# p2-101.net
KiCad netlist of a schematic drawn in EAGLE
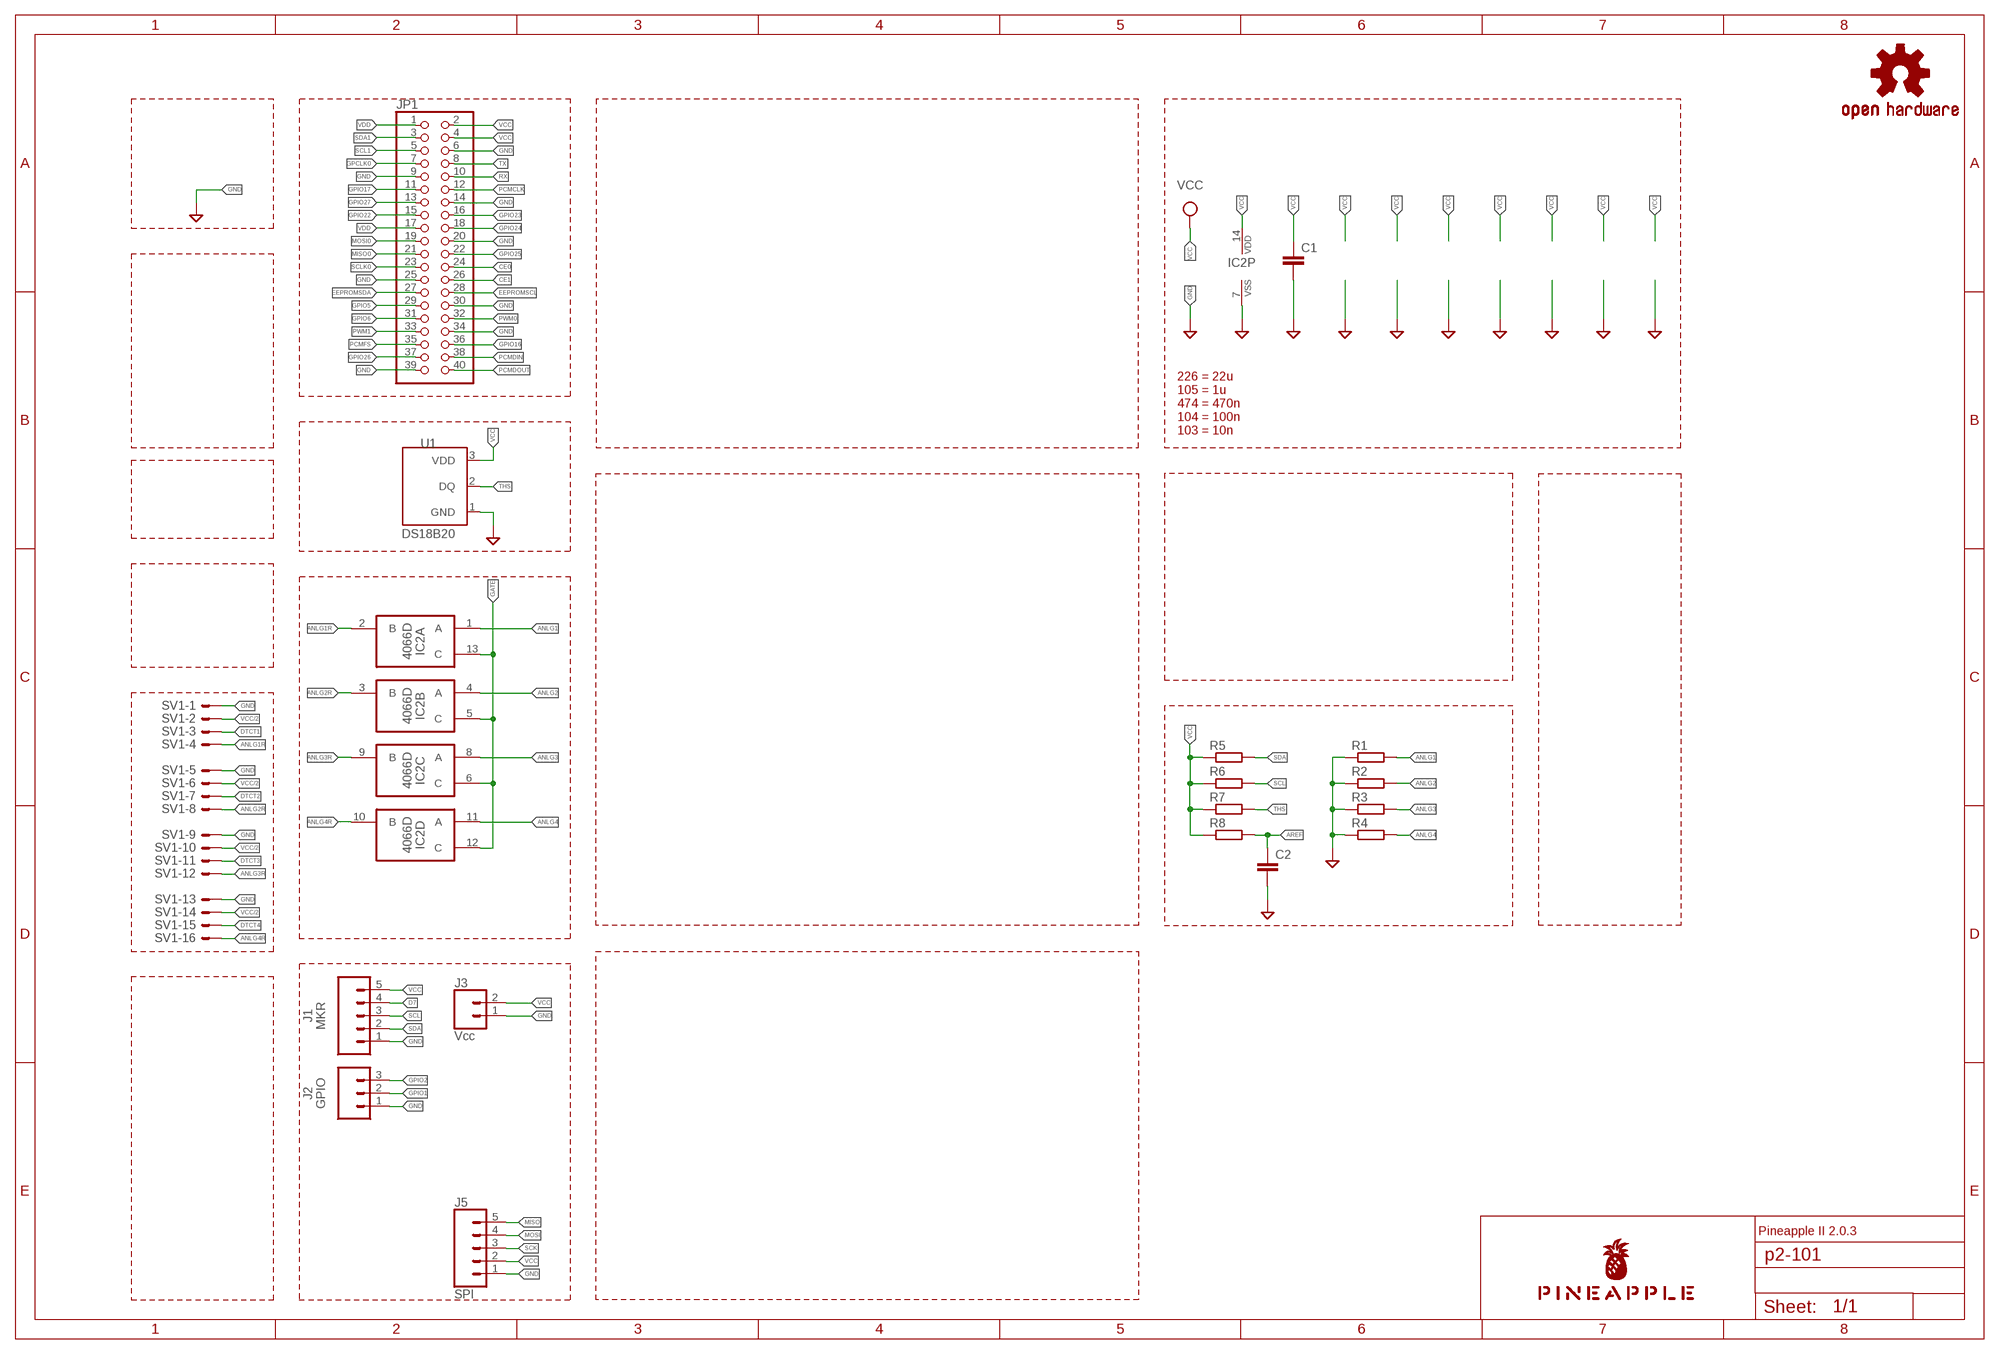
[diagram p0: schematic, sheet 1]

(export (version "E")
  (design (tool "Eeschema 10.0.6"))
  (components
    (comp (ref "C1")
      (value "C-EUC2012")
      (footprint "eagle-import:C2012")
      (libsource (lib "eagle-import") (part "C-EUC2012"))
    )
    (comp (ref "C2")
      (value "C-EUC2012")
      (footprint "eagle-import:C2012")
      (libsource (lib "eagle-import") (part "C-EUC2012"))
    )
    (comp (ref "IC2")
      (value "4066D")
      (footprint "eagle-import:SO14")
      (libsource (lib "eagle-import") (part "4066D"))
    )
    (comp (ref "J1")
      (value "MKR")
      (footprint "eagle-import:JST-5-PTH")
      (libsource (lib "eagle-import") (part "CONN_05JST"))
    )
    (comp (ref "J2")
      (value "GPIO")
      (footprint "eagle-import:JST-3-PTH")
      (libsource (lib "eagle-import") (part "CONN_03JST-PTH"))
    )
    (comp (ref "J3")
      (value "Vcc")
      (footprint "eagle-import:JST-2-PTH")
      (libsource (lib "eagle-import") (part "CONN_02JST-PTH-2"))
    )
    (comp (ref "J5")
      (value "SPI")
      (footprint "eagle-import:JST-5-PTH-VERT")
      (libsource (lib "eagle-import") (part "CONN_05JST-VERT"))
    )
    (comp (ref "JP1")
      (value "PINHD-2X20")
      (footprint "eagle-import:2X20")
      (libsource (lib "eagle-import") (part "PINHD-2X20"))
    )
    (comp (ref "LOGO1")
      (value "OSHW-LOGOS-COPPER")
      (footprint "eagle-import:OSHW-LOGO-S_COPPER")
      (libsource (lib "eagle-import") (part "OSHW-LOGOS-COPPER"))
    )
    (comp (ref "R1")
      (value "R-EU_M2012")
      (footprint "eagle-import:M2012")
      (libsource (lib "eagle-import") (part "R-EU_M2012"))
    )
    (comp (ref "R2")
      (value "R-EU_M2012")
      (footprint "eagle-import:M2012")
      (libsource (lib "eagle-import") (part "R-EU_M2012"))
    )
    (comp (ref "R3")
      (value "R-EU_M2012")
      (footprint "eagle-import:M2012")
      (libsource (lib "eagle-import") (part "R-EU_M2012"))
    )
    (comp (ref "R4")
      (value "R-EU_M2012")
      (footprint "eagle-import:M2012")
      (libsource (lib "eagle-import") (part "R-EU_M2012"))
    )
    (comp (ref "R5")
      (value "R-EU_M2012")
      (footprint "eagle-import:M2012")
      (libsource (lib "eagle-import") (part "R-EU_M2012"))
    )
    (comp (ref "R6")
      (value "R-EU_M2012")
      (footprint "eagle-import:M2012")
      (libsource (lib "eagle-import") (part "R-EU_M2012"))
    )
    (comp (ref "R7")
      (value "R-EU_M2012")
      (footprint "eagle-import:M2012")
      (libsource (lib "eagle-import") (part "R-EU_M2012"))
    )
    (comp (ref "R8")
      (value "R-EU_M2012")
      (footprint "eagle-import:M2012")
      (libsource (lib "eagle-import") (part "R-EU_M2012"))
    )
    (comp (ref "SV1")
      (value "ML16LE")
      (footprint "eagle-import:ML16L")
      (libsource (lib "eagle-import") (part "ML16LE"))
    )
    (comp (ref "U$1")
      (value "PINEAPPLE450_SILK")
      (footprint "eagle-import:PINEAPPLE450_SILK")
      (libsource (lib "eagle-import") (part "PINEAPPLE450_SILK"))
    )
    (comp (ref "U1")
      (value "DS18B20")
      (footprint "eagle-import:TO-92-AMMO")
      (libsource (lib "eagle-import") (part "DS18B20"))
    )
  )
  (nets
    (net (code "1") (name "ANLG1") (class "Default")
      (node (ref "IC2") (pin "1") (pinfunction "A_1") (pintype "tri_state"))
      (node (ref "R1") (pin "2") (pinfunction "2_2") (pintype "passive"))
    )
    (net (code "2") (name "ANLG1R") (class "Default")
      (node (ref "IC2") (pin "2") (pinfunction "B_2") (pintype "tri_state"))
      (node (ref "SV1") (pin "4") (pinfunction "S_4") (pintype "passive"))
    )
    (net (code "3") (name "ANLG2") (class "Default")
      (node (ref "IC2") (pin "4") (pinfunction "A_4") (pintype "tri_state"))
      (node (ref "R2") (pin "2") (pinfunction "2_2") (pintype "passive"))
    )
    (net (code "4") (name "ANLG2R") (class "Default")
      (node (ref "IC2") (pin "3") (pinfunction "B_3") (pintype "tri_state"))
      (node (ref "SV1") (pin "8") (pinfunction "S_8") (pintype "passive"))
    )
    (net (code "5") (name "ANLG3") (class "Default")
      (node (ref "IC2") (pin "8") (pinfunction "A_8") (pintype "tri_state"))
      (node (ref "R3") (pin "2") (pinfunction "2_2") (pintype "passive"))
    )
    (net (code "6") (name "ANLG3R") (class "Default")
      (node (ref "IC2") (pin "9") (pinfunction "B_9") (pintype "tri_state"))
      (node (ref "SV1") (pin "12") (pinfunction "S_12") (pintype "passive"))
    )
    (net (code "7") (name "ANLG4") (class "Default")
      (node (ref "IC2") (pin "11") (pinfunction "A_11") (pintype "tri_state"))
      (node (ref "R4") (pin "2") (pinfunction "2_2") (pintype "passive"))
    )
    (net (code "8") (name "ANLG4R") (class "Default")
      (node (ref "IC2") (pin "10") (pinfunction "B_10") (pintype "tri_state"))
      (node (ref "SV1") (pin "16") (pinfunction "S_16") (pintype "passive"))
    )
    (net (code "9") (name "AREF") (class "Default")
      (node (ref "C2") (pin "1") (pinfunction "1_1") (pintype "passive"))
      (node (ref "R8") (pin "2") (pinfunction "2_2") (pintype "passive"))
    )
    (net (code "10") (name "CE0") (class "Default")
      (node (ref "JP1") (pin "24") (pinfunction "24_24") (pintype "passive"))
    )
    (net (code "11") (name "CE1") (class "Default")
      (node (ref "JP1") (pin "26") (pinfunction "26_26") (pintype "passive"))
    )
    (net (code "12") (name "D7") (class "Default")
      (node (ref "J1") (pin "4") (pinfunction "4_4") (pintype "passive"))
    )
    (net (code "13") (name "DTCT1") (class "Default")
      (node (ref "SV1") (pin "3") (pinfunction "S_3") (pintype "passive"))
    )
    (net (code "14") (name "DTCT2") (class "Default")
      (node (ref "SV1") (pin "7") (pinfunction "S_7") (pintype "passive"))
    )
    (net (code "15") (name "DTCT3") (class "Default")
      (node (ref "SV1") (pin "11") (pinfunction "S_11") (pintype "passive"))
    )
    (net (code "16") (name "DTCT4") (class "Default")
      (node (ref "SV1") (pin "15") (pinfunction "S_15") (pintype "passive"))
    )
    (net (code "17") (name "EEPROMSCL") (class "Default")
      (node (ref "JP1") (pin "28") (pinfunction "28_28") (pintype "passive"))
    )
    (net (code "18") (name "EEPROMSDA") (class "Default")
      (node (ref "JP1") (pin "27") (pinfunction "27_27") (pintype "passive"))
    )
    (net (code "19") (name "GATE") (class "Default")
      (node (ref "IC2") (pin "12") (pinfunction "C_12") (pintype "input"))
      (node (ref "IC2") (pin "13") (pinfunction "C_13") (pintype "input"))
      (node (ref "IC2") (pin "5") (pinfunction "C_5") (pintype "input"))
      (node (ref "IC2") (pin "6") (pinfunction "C_6") (pintype "input"))
    )
    (net (code "20") (name "GND") (class "Default")
      (node (ref "C1") (pin "2") (pinfunction "2_2") (pintype "passive"))
      (node (ref "C2") (pin "2") (pinfunction "2_2") (pintype "passive"))
      (node (ref "IC2") (pin "7") (pinfunction "VSS_7") (pintype "power_in"))
      (node (ref "J1") (pin "1") (pinfunction "1_1") (pintype "passive"))
      (node (ref "J2") (pin "1") (pinfunction "1_1") (pintype "passive"))
      (node (ref "J3") (pin "1") (pinfunction "1_1") (pintype "passive"))
      (node (ref "J5") (pin "1") (pinfunction "1_1") (pintype "passive"))
      (node (ref "JP1") (pin "14") (pinfunction "14_14") (pintype "passive"))
      (node (ref "JP1") (pin "20") (pinfunction "20_20") (pintype "passive"))
      (node (ref "JP1") (pin "25") (pinfunction "25_25") (pintype "passive"))
      (node (ref "JP1") (pin "30") (pinfunction "30_30") (pintype "passive"))
      (node (ref "JP1") (pin "34") (pinfunction "34_34") (pintype "passive"))
      (node (ref "JP1") (pin "39") (pinfunction "39_39") (pintype "passive"))
      (node (ref "JP1") (pin "6") (pinfunction "6_6") (pintype "passive"))
      (node (ref "JP1") (pin "9") (pinfunction "9_9") (pintype "passive"))
      (node (ref "R1") (pin "1") (pinfunction "1_1") (pintype "passive"))
      (node (ref "R2") (pin "1") (pinfunction "1_1") (pintype "passive"))
      (node (ref "R3") (pin "1") (pinfunction "1_1") (pintype "passive"))
      (node (ref "R4") (pin "1") (pinfunction "1_1") (pintype "passive"))
      (node (ref "SV1") (pin "1") (pinfunction "S_1") (pintype "passive"))
      (node (ref "SV1") (pin "13") (pinfunction "S_13") (pintype "passive"))
      (node (ref "SV1") (pin "5") (pinfunction "S_5") (pintype "passive"))
      (node (ref "SV1") (pin "9") (pinfunction "S_9") (pintype "passive"))
      (node (ref "U1") (pin "1") (pinfunction "GND_1") (pintype "power_in"))
    )
    (net (code "21") (name "GPCLK0") (class "Default")
      (node (ref "JP1") (pin "7") (pinfunction "7_7") (pintype "passive"))
    )
    (net (code "22") (name "GPIO1") (class "Default")
      (node (ref "J2") (pin "2") (pinfunction "2_2") (pintype "passive"))
    )
    (net (code "23") (name "GPIO2") (class "Default")
      (node (ref "J2") (pin "3") (pinfunction "3_3") (pintype "passive"))
    )
    (net (code "24") (name "GPIO5") (class "Default")
      (node (ref "JP1") (pin "29") (pinfunction "29_29") (pintype "passive"))
    )
    (net (code "25") (name "GPIO6") (class "Default")
      (node (ref "JP1") (pin "31") (pinfunction "31_31") (pintype "passive"))
    )
    (net (code "26") (name "GPIO16") (class "Default")
      (node (ref "JP1") (pin "36") (pinfunction "36_36") (pintype "passive"))
    )
    (net (code "27") (name "GPIO17") (class "Default")
      (node (ref "JP1") (pin "11") (pinfunction "11_11") (pintype "passive"))
    )
    (net (code "28") (name "GPIO22") (class "Default")
      (node (ref "JP1") (pin "15") (pinfunction "15_15") (pintype "passive"))
    )
    (net (code "29") (name "GPIO23") (class "Default")
      (node (ref "JP1") (pin "16") (pinfunction "16_16") (pintype "passive"))
    )
    (net (code "30") (name "GPIO24") (class "Default")
      (node (ref "JP1") (pin "18") (pinfunction "18_18") (pintype "passive"))
    )
    (net (code "31") (name "GPIO25") (class "Default")
      (node (ref "JP1") (pin "22") (pinfunction "22_22") (pintype "passive"))
    )
    (net (code "32") (name "GPIO26") (class "Default")
      (node (ref "JP1") (pin "37") (pinfunction "37_37") (pintype "passive"))
    )
    (net (code "33") (name "GPIO27") (class "Default")
      (node (ref "JP1") (pin "13") (pinfunction "13_13") (pintype "passive"))
    )
    (net (code "34") (name "MISO") (class "Default")
      (node (ref "J5") (pin "5") (pinfunction "5_5") (pintype "passive"))
    )
    (net (code "35") (name "MISO0") (class "Default")
      (node (ref "JP1") (pin "21") (pinfunction "21_21") (pintype "passive"))
    )
    (net (code "36") (name "MOSI") (class "Default")
      (node (ref "J5") (pin "4") (pinfunction "4_4") (pintype "passive"))
    )
    (net (code "37") (name "MOSI0") (class "Default")
      (node (ref "JP1") (pin "19") (pinfunction "19_19") (pintype "passive"))
    )
    (net (code "38") (name "PCMCLK") (class "Default")
      (node (ref "JP1") (pin "12") (pinfunction "12_12") (pintype "passive"))
    )
    (net (code "39") (name "PCMDIN") (class "Default")
      (node (ref "JP1") (pin "38") (pinfunction "38_38") (pintype "passive"))
    )
    (net (code "40") (name "PCMDOUT") (class "Default")
      (node (ref "JP1") (pin "40") (pinfunction "40_40") (pintype "passive"))
    )
    (net (code "41") (name "PCMFS") (class "Default")
      (node (ref "JP1") (pin "35") (pinfunction "35_35") (pintype "passive"))
    )
    (net (code "42") (name "PWM0") (class "Default")
      (node (ref "JP1") (pin "32") (pinfunction "32_32") (pintype "passive"))
    )
    (net (code "43") (name "PWM1") (class "Default")
      (node (ref "JP1") (pin "33") (pinfunction "33_33") (pintype "passive"))
    )
    (net (code "44") (name "RX") (class "Default")
      (node (ref "JP1") (pin "10") (pinfunction "10_10") (pintype "passive"))
    )
    (net (code "45") (name "SCK") (class "Default")
      (node (ref "J5") (pin "3") (pinfunction "3_3") (pintype "passive"))
    )
    (net (code "46") (name "SCL") (class "Default")
      (node (ref "J1") (pin "3") (pinfunction "3_3") (pintype "passive"))
      (node (ref "R6") (pin "2") (pinfunction "2_2") (pintype "passive"))
    )
    (net (code "47") (name "SCL1") (class "Default")
      (node (ref "JP1") (pin "5") (pinfunction "5_5") (pintype "passive"))
    )
    (net (code "48") (name "SCLK0") (class "Default")
      (node (ref "JP1") (pin "23") (pinfunction "23_23") (pintype "passive"))
    )
    (net (code "49") (name "SDA") (class "Default")
      (node (ref "J1") (pin "2") (pinfunction "2_2") (pintype "passive"))
      (node (ref "R5") (pin "2") (pinfunction "2_2") (pintype "passive"))
    )
    (net (code "50") (name "SDA1") (class "Default")
      (node (ref "JP1") (pin "3") (pinfunction "3_3") (pintype "passive"))
    )
    (net (code "51") (name "THS") (class "Default")
      (node (ref "R7") (pin "2") (pinfunction "2_2") (pintype "passive"))
      (node (ref "U1") (pin "2") (pinfunction "DQ_2") (pintype "bidirectional"))
    )
    (net (code "52") (name "TX") (class "Default")
      (node (ref "JP1") (pin "8") (pinfunction "8_8") (pintype "passive"))
    )
    (net (code "53") (name "VCC") (class "Default")
      (node (ref "C1") (pin "1") (pinfunction "1_1") (pintype "passive"))
      (node (ref "IC2") (pin "14") (pinfunction "VDD_14") (pintype "power_in"))
      (node (ref "J1") (pin "5") (pinfunction "5_5") (pintype "passive"))
      (node (ref "J3") (pin "2") (pinfunction "2_2") (pintype "passive"))
      (node (ref "J5") (pin "2") (pinfunction "2_2") (pintype "passive"))
      (node (ref "JP1") (pin "2") (pinfunction "2_2") (pintype "passive"))
      (node (ref "JP1") (pin "4") (pinfunction "4_4") (pintype "passive"))
      (node (ref "R5") (pin "1") (pinfunction "1_1") (pintype "passive"))
      (node (ref "R6") (pin "1") (pinfunction "1_1") (pintype "passive"))
      (node (ref "R7") (pin "1") (pinfunction "1_1") (pintype "passive"))
      (node (ref "R8") (pin "1") (pinfunction "1_1") (pintype "passive"))
      (node (ref "U1") (pin "3") (pinfunction "VDD_3") (pintype "power_in"))
    )
    (net (code "54") (name "VCC{slash}2") (class "Default")
      (node (ref "SV1") (pin "10") (pinfunction "S_10") (pintype "passive"))
      (node (ref "SV1") (pin "14") (pinfunction "S_14") (pintype "passive"))
      (node (ref "SV1") (pin "2") (pinfunction "S_2") (pintype "passive"))
      (node (ref "SV1") (pin "6") (pinfunction "S_6") (pintype "passive"))
    )
    (net (code "55") (name "VDD") (class "Default")
      (node (ref "JP1") (pin "1") (pinfunction "1_1") (pintype "passive"))
      (node (ref "JP1") (pin "17") (pinfunction "17_17") (pintype "passive"))
    )
  )
)
